# PB32_3_x.net
KiCad netlist of a schematic drawn in EAGLE
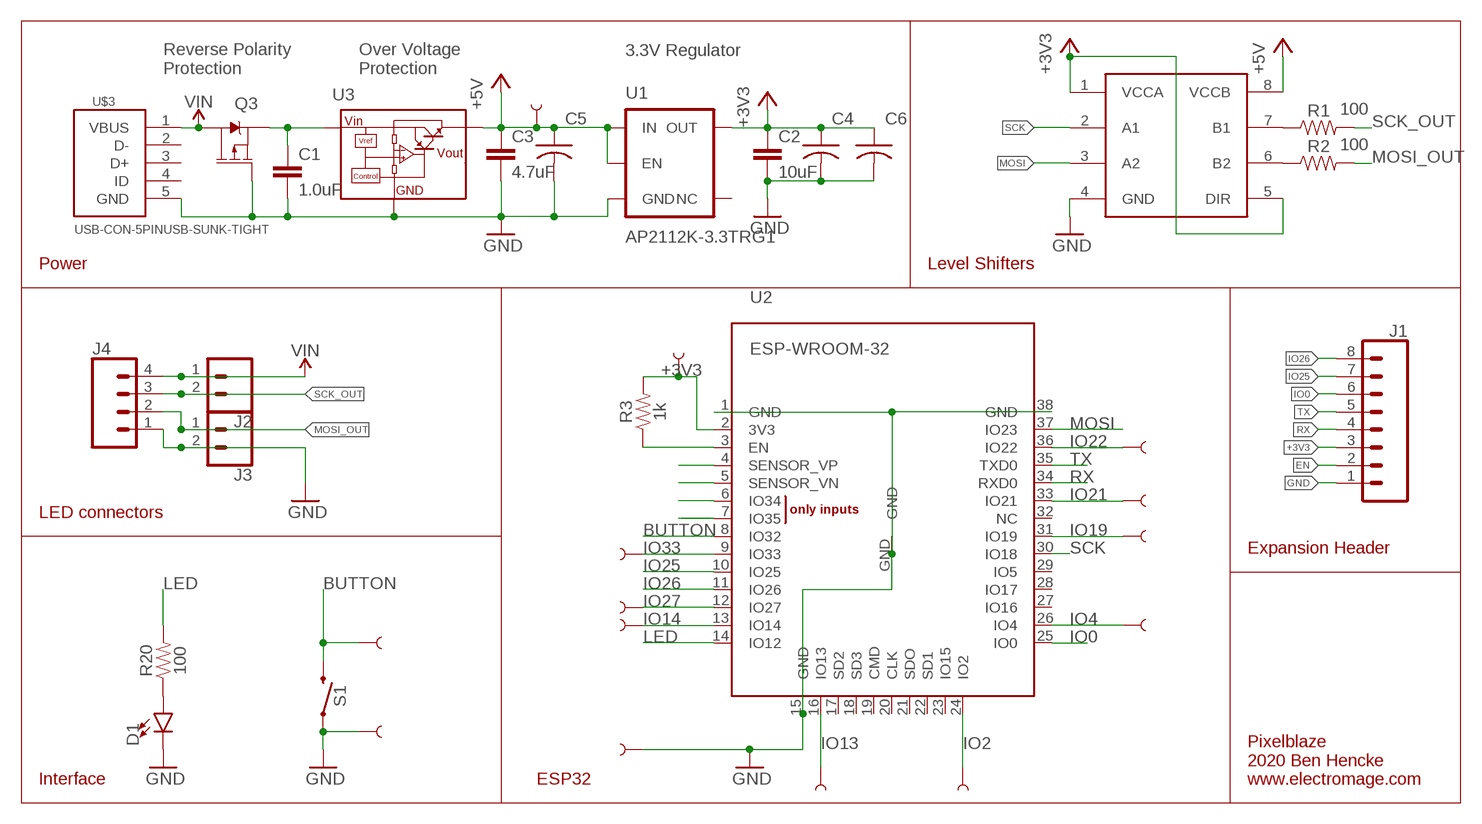
[diagram p0: schematic, sheet 1]

(export (version "E")
  (design (tool "Eeschema 10.0.6"))
  (components
    (comp (ref "C1")
      (value "1.0uF")
      (footprint "eagle-import:0805-CAP")
      (libsource (lib "eagle-import") (part "1.0UF-25V-+80/-20(0805){dblquote}"))
    )
    (comp (ref "C2")
      (value "10uF")
      (footprint "eagle-import:0805")
      (libsource (lib "eagle-import") (part "10UF-0805-10V-10%"))
    )
    (comp (ref "C3")
      (value "4.7uF")
      (footprint "eagle-import:0603")
      (libsource (lib "eagle-import") (part "4.7UF0603"))
    )
    (comp (ref "C4")
      (value "0.1uF")
      (footprint "eagle-import:C0402K")
      (libsource (lib "eagle-import") (part "C-USC0402K"))
    )
    (comp (ref "C5")
      (value "0.1uF")
      (footprint "eagle-import:C0402K")
      (libsource (lib "eagle-import") (part "C-USC0402K"))
    )
    (comp (ref "C6")
      (value "0.1uF")
      (footprint "eagle-import:C0402K")
      (libsource (lib "eagle-import") (part "C-USC0402K"))
    )
    (comp (ref "D1")
      (value "LED0603")
      (footprint "eagle-import:LED-0603")
      (libsource (lib "eagle-import") (part "LED0603"))
    )
    (comp (ref "GP1")
      (value "SMTPAD")
      (footprint "eagle-import:PAD")
      (libsource (lib "eagle-import") (part "SMTPAD"))
    )
    (comp (ref "GP3")
      (value "SMTPAD")
      (footprint "eagle-import:PAD")
      (libsource (lib "eagle-import") (part "SMTPAD"))
    )
    (comp (ref "GP6")
      (value "SMTPAD")
      (footprint "eagle-import:PAD")
      (libsource (lib "eagle-import") (part "SMTPAD"))
    )
    (comp (ref "GP8")
      (value "SMTPAD")
      (footprint "eagle-import:PAD")
      (libsource (lib "eagle-import") (part "SMTPAD"))
    )
    (comp (ref "GP9")
      (value "SMTPAD")
      (footprint "eagle-import:PAD")
      (libsource (lib "eagle-import") (part "SMTPAD"))
    )
    (comp (ref "IO2")
      (value "SMTPAD")
      (footprint "eagle-import:PAD")
      (libsource (lib "eagle-import") (part "SMTPAD"))
    )
    (comp (ref "IO4")
      (value "SMTPAD")
      (footprint "eagle-import:PAD")
      (libsource (lib "eagle-import") (part "SMTPAD"))
    )
    (comp (ref "IO13")
      (value "SMTPAD")
      (footprint "eagle-import:PAD")
      (libsource (lib "eagle-import") (part "SMTPAD"))
    )
    (comp (ref "IO14")
      (value "SMTPAD")
      (footprint "eagle-import:PAD")
      (libsource (lib "eagle-import") (part "SMTPAD"))
    )
    (comp (ref "IO19")
      (value "SMTPAD")
      (footprint "eagle-import:PAD")
      (libsource (lib "eagle-import") (part "SMTPAD"))
    )
    (comp (ref "IO21")
      (value "SMTPAD")
      (footprint "eagle-import:PAD")
      (libsource (lib "eagle-import") (part "SMTPAD"))
    )
    (comp (ref "IO22")
      (value "SMTPAD")
      (footprint "eagle-import:PAD")
      (libsource (lib "eagle-import") (part "SMTPAD"))
    )
    (comp (ref "IO27")
      (value "SMTPAD")
      (footprint "eagle-import:PAD")
      (libsource (lib "eagle-import") (part "SMTPAD"))
    )
    (comp (ref "IO33")
      (value "SMTPAD")
      (footprint "eagle-import:PAD")
      (libsource (lib "eagle-import") (part "SMTPAD"))
    )
    (comp (ref "J1")
      (value "CONN_08LOCK")
      (footprint "eagle-import:1X08_LOCK")
      (libsource (lib "eagle-import") (part "CONN_08LOCK"))
    )
    (comp (ref "J2")
      (value "CONN_025MM")
      (footprint "eagle-import:SCREWTERMINAL-5MM-2")
      (libsource (lib "eagle-import") (part "CONN_025MM"))
    )
    (comp (ref "J3")
      (value "CONN_025MM")
      (footprint "eagle-import:SCREWTERMINAL-5MM-2")
      (libsource (lib "eagle-import") (part "CONN_025MM"))
    )
    (comp (ref "J4")
      (value "CONN_041X04_NO_SILK")
      (footprint "eagle-import:1X04_NO_SILK")
      (libsource (lib "eagle-import") (part "CONN_041X04_NO_SILK"))
    )
    (comp (ref "Q3")
      (value "2.5A/30V/105mΩ")
      (footprint "eagle-import:SOT23-3")
      (libsource (lib "eagle-import") (part "MOSFET_PCH-DMG2307L"))
    )
    (comp (ref "R1")
      (value "100")
      (footprint "eagle-import:0603")
      (libsource (lib "eagle-import") (part "100OHM-0603-1/10W-1%"))
    )
    (comp (ref "R2")
      (value "100")
      (footprint "eagle-import:0603")
      (libsource (lib "eagle-import") (part "100OHM-0603-1/10W-1%"))
    )
    (comp (ref "R3")
      (value "1k")
      (footprint "eagle-import:0603")
      (libsource (lib "eagle-import") (part "1KOHM-0603-1/10W-1%"))
    )
    (comp (ref "R20")
      (value "100")
      (footprint "eagle-import:0603")
      (libsource (lib "eagle-import") (part "100OHM-0603-1/10W-1%"))
    )
    (comp (ref "S1")
      (value "MOMENTARY-SWITCH-SPST-SMD-5.2MM")
      (footprint "eagle-import:TACTILE_SWITCH_SMD_5.2MM")
      (libsource (lib "eagle-import") (part "MOMENTARY-SWITCH-SPST-SMD-5.2MM"))
    )
    (comp (ref "U$1")
      (value "SN74LVC2T45DCUR")
      (footprint "eagle-import:SOP50P310X90-8N")
      (libsource (lib "eagle-import") (part "SN74LVC2T45DCUR"))
    )
    (comp (ref "U$3")
      (value "USB-CON-5PINUSB-SUNK-TIGHT")
      (footprint "eagle-import:USB-SUNK-TIGHT")
      (libsource (lib "eagle-import") (part "USB-CON-5PINUSB-SUNK-TIGHT"))
    )
    (comp (ref "U1")
      (value "AP2112K-3.3TRG1")
      (footprint "eagle-import:SOT23-5")
      (libsource (lib "eagle-import") (part "V_REG_AP2112K-3.3V"))
    )
    (comp (ref "U2")
      (value "ESP-WROOM-32")
      (footprint "eagle-import:ESP-WROOM-32")
      (libsource (lib "eagle-import") (part "ESP-WROOM-32"))
    )
    (comp (ref "U3")
      (value "NX1117C15Z")
      (footprint "eagle-import:SOT223")
      (fields (field (name "TOLERANCE") "1.25%") (field (name "VOLTAGE") "5.0V"))
      (libsource (lib "eagle-import") (part "NX1117CZ15"))
    )
  )
  (nets
    (net (code "1") (name "+3V3") (class "Default")
      (node (ref "C2") (pin "1") (pinfunction "1_1") (pintype "passive"))
      (node (ref "C4") (pin "1") (pinfunction "1_1") (pintype "passive"))
      (node (ref "C6") (pin "1") (pinfunction "1_1") (pintype "passive"))
      (node (ref "GP1") (pin "P$1") (pinfunction "1_P$1") (pintype "bidirectional"))
      (node (ref "J1") (pin "3") (pinfunction "3_3") (pintype "passive"))
      (node (ref "R3") (pin "2") (pinfunction "2_2") (pintype "passive"))
      (node (ref "U$1") (pin "1") (pinfunction "VCCA_1") (pintype "bidirectional"))
      (node (ref "U$1") (pin "5") (pinfunction "DIR_5") (pintype "bidirectional"))
      (node (ref "U1") (pin "5") (pinfunction "OUT_5") (pintype "passive"))
      (node (ref "U2") (pin "2") (pinfunction "3V3_2") (pintype "bidirectional"))
    )
    (net (code "2") (name "+5V") (class "Default")
      (node (ref "C3") (pin "1") (pinfunction "1_1") (pintype "passive"))
      (node (ref "C5") (pin "1") (pinfunction "1_1") (pintype "passive"))
      (node (ref "GP6") (pin "P$1") (pinfunction "1_P$1") (pintype "bidirectional"))
      (node (ref "U$1") (pin "8") (pinfunction "VCCB_8") (pintype "bidirectional"))
      (node (ref "U1") (pin "1") (pinfunction "IN_1") (pintype "input"))
      (node (ref "U1") (pin "3") (pinfunction "EN_3") (pintype "input"))
      (node (ref "U3") (pin "2") (pinfunction "VOUT_2") (pintype "output"))
      (node (ref "U3") (pin "4") (pinfunction "VOUT_4") (pintype "output"))
    )
    (net (code "3") (name "/BUTTON") (class "Default")
      (node (ref "GP8") (pin "P$1") (pinfunction "1_P$1") (pintype "bidirectional"))
      (node (ref "S1") (pin "3") (pinfunction "2_3") (pintype "passive"))
      (node (ref "U2") (pin "8") (pinfunction "IO32_8") (pintype "bidirectional"))
    )
    (net (code "4") (name "/IO2") (class "Default")
      (node (ref "IO2") (pin "P$1") (pinfunction "1_P$1") (pintype "bidirectional"))
      (node (ref "U2") (pin "24") (pinfunction "IO2_24") (pintype "bidirectional"))
    )
    (net (code "5") (name "/IO4") (class "Default")
      (node (ref "IO4") (pin "P$1") (pinfunction "1_P$1") (pintype "bidirectional"))
      (node (ref "U2") (pin "26") (pinfunction "IO4_26") (pintype "bidirectional"))
    )
    (net (code "6") (name "/IO13") (class "Default")
      (node (ref "IO13") (pin "P$1") (pinfunction "1_P$1") (pintype "bidirectional"))
      (node (ref "U2") (pin "16") (pinfunction "IO13_16") (pintype "bidirectional"))
    )
    (net (code "7") (name "/IO14") (class "Default")
      (node (ref "IO14") (pin "P$1") (pinfunction "1_P$1") (pintype "bidirectional"))
      (node (ref "U2") (pin "13") (pinfunction "IO14_13") (pintype "bidirectional"))
    )
    (net (code "8") (name "/IO19") (class "Default")
      (node (ref "IO19") (pin "P$1") (pinfunction "1_P$1") (pintype "bidirectional"))
      (node (ref "U2") (pin "31") (pinfunction "IO19_31") (pintype "bidirectional"))
    )
    (net (code "9") (name "/IO21") (class "Default")
      (node (ref "IO21") (pin "P$1") (pinfunction "1_P$1") (pintype "bidirectional"))
      (node (ref "U2") (pin "33") (pinfunction "IO21_33") (pintype "bidirectional"))
    )
    (net (code "10") (name "/IO22") (class "Default")
      (node (ref "IO22") (pin "P$1") (pinfunction "1_P$1") (pintype "bidirectional"))
      (node (ref "U2") (pin "36") (pinfunction "IO22_36") (pintype "bidirectional"))
    )
    (net (code "11") (name "/IO27") (class "Default")
      (node (ref "IO27") (pin "P$1") (pinfunction "1_P$1") (pintype "bidirectional"))
      (node (ref "U2") (pin "12") (pinfunction "IO27_12") (pintype "bidirectional"))
    )
    (net (code "12") (name "/IO33") (class "Default")
      (node (ref "IO33") (pin "P$1") (pinfunction "1_P$1") (pintype "bidirectional"))
      (node (ref "U2") (pin "9") (pinfunction "IO33_9") (pintype "bidirectional"))
    )
    (net (code "13") (name "/LED") (class "Default")
      (node (ref "R20") (pin "2") (pinfunction "2_2") (pintype "passive"))
      (node (ref "U2") (pin "14") (pinfunction "IO12_14") (pintype "bidirectional"))
    )
    (net (code "14") (name "EN") (class "Default")
      (node (ref "J1") (pin "2") (pinfunction "2_2") (pintype "passive"))
      (node (ref "R3") (pin "1") (pinfunction "1_1") (pintype "passive"))
      (node (ref "U2") (pin "3") (pinfunction "EN_3") (pintype "bidirectional"))
    )
    (net (code "15") (name "GND") (class "Default")
      (node (ref "C1") (pin "2") (pinfunction "2_2") (pintype "passive"))
      (node (ref "C2") (pin "2") (pinfunction "2_2") (pintype "passive"))
      (node (ref "C3") (pin "2") (pinfunction "2_2") (pintype "passive"))
      (node (ref "C4") (pin "2") (pinfunction "2_2") (pintype "passive"))
      (node (ref "C5") (pin "2") (pinfunction "2_2") (pintype "passive"))
      (node (ref "C6") (pin "2") (pinfunction "2_2") (pintype "passive"))
      (node (ref "D1") (pin "C") (pinfunction "C_C") (pintype "passive"))
      (node (ref "GP3") (pin "P$1") (pinfunction "1_P$1") (pintype "bidirectional"))
      (node (ref "GP9") (pin "P$1") (pinfunction "1_P$1") (pintype "bidirectional"))
      (node (ref "J1") (pin "1") (pinfunction "1_1") (pintype "passive"))
      (node (ref "J3") (pin "2") (pinfunction "2_2") (pintype "passive"))
      (node (ref "J4") (pin "1") (pinfunction "1_1") (pintype "passive"))
      (node (ref "Q3") (pin "1") (pinfunction "G_1") (pintype "bidirectional"))
      (node (ref "S1") (pin "1") (pinfunction "1_1") (pintype "passive"))
      (node (ref "U$1") (pin "4") (pinfunction "GND_4") (pintype "bidirectional"))
      (node (ref "U$3") (pin "5") (pinfunction "GND_5") (pintype "power_in"))
      (node (ref "U1") (pin "2") (pinfunction "GND_2") (pintype "input"))
      (node (ref "U2") (pin "1") (pinfunction "GND_1") (pintype "bidirectional"))
      (node (ref "U2") (pin "15") (pinfunction "GND_15") (pintype "bidirectional"))
      (node (ref "U2") (pin "38") (pinfunction "GND_38") (pintype "bidirectional"))
      (node (ref "U2") (pin "GND") (pinfunction "GND_GND") (pintype "bidirectional"))
      (node (ref "U3") (pin "1") (pinfunction "GND_1") (pintype "passive"))
    )
    (net (code "16") (name "IO0") (class "Default")
      (node (ref "J1") (pin "6") (pinfunction "6_6") (pintype "passive"))
      (node (ref "U2") (pin "25") (pinfunction "IO0_25") (pintype "bidirectional"))
    )
    (net (code "17") (name "IO25") (class "Default")
      (node (ref "J1") (pin "7") (pinfunction "7_7") (pintype "passive"))
      (node (ref "U2") (pin "10") (pinfunction "IO25_10") (pintype "bidirectional"))
    )
    (net (code "18") (name "IO26") (class "Default")
      (node (ref "J1") (pin "8") (pinfunction "8_8") (pintype "passive"))
      (node (ref "U2") (pin "11") (pinfunction "IO26_11") (pintype "bidirectional"))
    )
    (net (code "19") (name "MOSI") (class "Default")
      (node (ref "U$1") (pin "3") (pinfunction "A2_3") (pintype "bidirectional"))
      (node (ref "U2") (pin "37") (pinfunction "IO23_37") (pintype "bidirectional"))
    )
    (net (code "20") (name "MOSI_OUT") (class "Default")
      (node (ref "J3") (pin "1") (pinfunction "1_1") (pintype "passive"))
      (node (ref "J4") (pin "2") (pinfunction "2_2") (pintype "passive"))
      (node (ref "R2") (pin "2") (pinfunction "2_2") (pintype "passive"))
    )
    (net (code "21") (name "Net-(D1-PadA)") (class "Default")
      (node (ref "D1") (pin "A") (pinfunction "A_A") (pintype "passive"))
      (node (ref "R20") (pin "1") (pinfunction "1_1") (pintype "passive"))
    )
    (net (code "22") (name "Net-(Q3-S)") (class "Default")
      (node (ref "C1") (pin "1") (pinfunction "1_1") (pintype "passive"))
      (node (ref "Q3") (pin "2") (pinfunction "S_2") (pintype "bidirectional"))
      (node (ref "U3") (pin "3") (pinfunction "VIN_3") (pintype "input"))
    )
    (net (code "23") (name "Net-(U$1-B1)") (class "Default")
      (node (ref "R1") (pin "1") (pinfunction "1_1") (pintype "passive"))
      (node (ref "U$1") (pin "7") (pinfunction "B1_7") (pintype "bidirectional"))
    )
    (net (code "24") (name "Net-(U$1-B2)") (class "Default")
      (node (ref "R2") (pin "1") (pinfunction "1_1") (pintype "passive"))
      (node (ref "U$1") (pin "6") (pinfunction "B2_6") (pintype "bidirectional"))
    )
    (net (code "25") (name "RX") (class "Default")
      (node (ref "J1") (pin "4") (pinfunction "4_4") (pintype "passive"))
      (node (ref "U2") (pin "34") (pinfunction "RXD0_34") (pintype "bidirectional"))
    )
    (net (code "26") (name "SCK") (class "Default")
      (node (ref "U$1") (pin "2") (pinfunction "A1_2") (pintype "bidirectional"))
      (node (ref "U2") (pin "30") (pinfunction "IO18_30") (pintype "bidirectional"))
    )
    (net (code "27") (name "SCK_OUT") (class "Default")
      (node (ref "J2") (pin "2") (pinfunction "2_2") (pintype "passive"))
      (node (ref "J4") (pin "3") (pinfunction "3_3") (pintype "passive"))
      (node (ref "R1") (pin "2") (pinfunction "2_2") (pintype "passive"))
    )
    (net (code "28") (name "TX") (class "Default")
      (node (ref "J1") (pin "5") (pinfunction "5_5") (pintype "passive"))
      (node (ref "U2") (pin "35") (pinfunction "TXD0_35") (pintype "bidirectional"))
    )
    (net (code "29") (name "VIN") (class "Default")
      (node (ref "J2") (pin "1") (pinfunction "1_1") (pintype "passive"))
      (node (ref "J4") (pin "4") (pinfunction "4_4") (pintype "passive"))
      (node (ref "Q3") (pin "3") (pinfunction "D_3") (pintype "bidirectional"))
      (node (ref "U$3") (pin "1") (pinfunction "VBUS_1") (pintype "power_in"))
    )
    (net (code "30") (name "unconnected-(U$3-D+-Pad3)") (class "Default")
      (node (ref "U$3") (pin "3") (pinfunction "D+_3") (pintype "bidirectional"))
    )
    (net (code "31") (name "unconnected-(U$3-D--Pad2)") (class "Default")
      (node (ref "U$3") (pin "2") (pinfunction "D-_2") (pintype "bidirectional"))
    )
    (net (code "32") (name "unconnected-(U$3-ID-Pad4)") (class "Default")
      (node (ref "U$3") (pin "4") (pinfunction "ID_4") (pintype "bidirectional"))
    )
    (net (code "33") (name "unconnected-(U1-NC-Pad4)") (class "Default")
      (node (ref "U1") (pin "4") (pinfunction "NC_4") (pintype "input"))
    )
    (net (code "34") (name "unconnected-(U2-CLK-Pad20)") (class "Default")
      (node (ref "U2") (pin "20") (pinfunction "CLK_20") (pintype "bidirectional"))
    )
    (net (code "35") (name "unconnected-(U2-CMD-Pad19)") (class "Default")
      (node (ref "U2") (pin "19") (pinfunction "CMD_19") (pintype "bidirectional"))
    )
    (net (code "36") (name "unconnected-(U2-IO5-Pad29)") (class "Default")
      (node (ref "U2") (pin "29") (pinfunction "IO5_29") (pintype "bidirectional"))
    )
    (net (code "37") (name "unconnected-(U2-IO15-Pad23)") (class "Default")
      (node (ref "U2") (pin "23") (pinfunction "IO15_23") (pintype "bidirectional"))
    )
    (net (code "38") (name "unconnected-(U2-IO16-Pad27)") (class "Default")
      (node (ref "U2") (pin "27") (pinfunction "IO16_27") (pintype "bidirectional"))
    )
    (net (code "39") (name "unconnected-(U2-IO17-Pad28)") (class "Default")
      (node (ref "U2") (pin "28") (pinfunction "IO17_28") (pintype "bidirectional"))
    )
    (net (code "40") (name "unconnected-(U2-IO34-Pad6)") (class "Default")
      (node (ref "U2") (pin "6") (pinfunction "IO34_6") (pintype "input"))
    )
    (net (code "41") (name "unconnected-(U2-IO35-Pad7)") (class "Default")
      (node (ref "U2") (pin "7") (pinfunction "IO35_7") (pintype "input"))
    )
    (net (code "42") (name "unconnected-(U2-NC-Pad32)") (class "Default")
      (node (ref "U2") (pin "32") (pinfunction "NC_32") (pintype "bidirectional"))
    )
    (net (code "43") (name "unconnected-(U2-SD1-Pad22)") (class "Default")
      (node (ref "U2") (pin "22") (pinfunction "SD1_22") (pintype "bidirectional"))
    )
    (net (code "44") (name "unconnected-(U2-SD2-Pad17)") (class "Default")
      (node (ref "U2") (pin "17") (pinfunction "SD2_17") (pintype "bidirectional"))
    )
    (net (code "45") (name "unconnected-(U2-SD3-Pad18)") (class "Default")
      (node (ref "U2") (pin "18") (pinfunction "SD3_18") (pintype "bidirectional"))
    )
    (net (code "46") (name "unconnected-(U2-SDO-Pad21)") (class "Default")
      (node (ref "U2") (pin "21") (pinfunction "SDO_21") (pintype "bidirectional"))
    )
    (net (code "47") (name "unconnected-(U2-SENSOR_VN-Pad5)") (class "Default")
      (node (ref "U2") (pin "5") (pinfunction "SENSOR_VN_5") (pintype "input"))
    )
    (net (code "48") (name "unconnected-(U2-SENSOR_VP-Pad4)") (class "Default")
      (node (ref "U2") (pin "4") (pinfunction "SENSOR_VP_4") (pintype "input"))
    )
  )
)
